# ALARM.net
KiCad netlist of a schematic drawn in Altium Designer
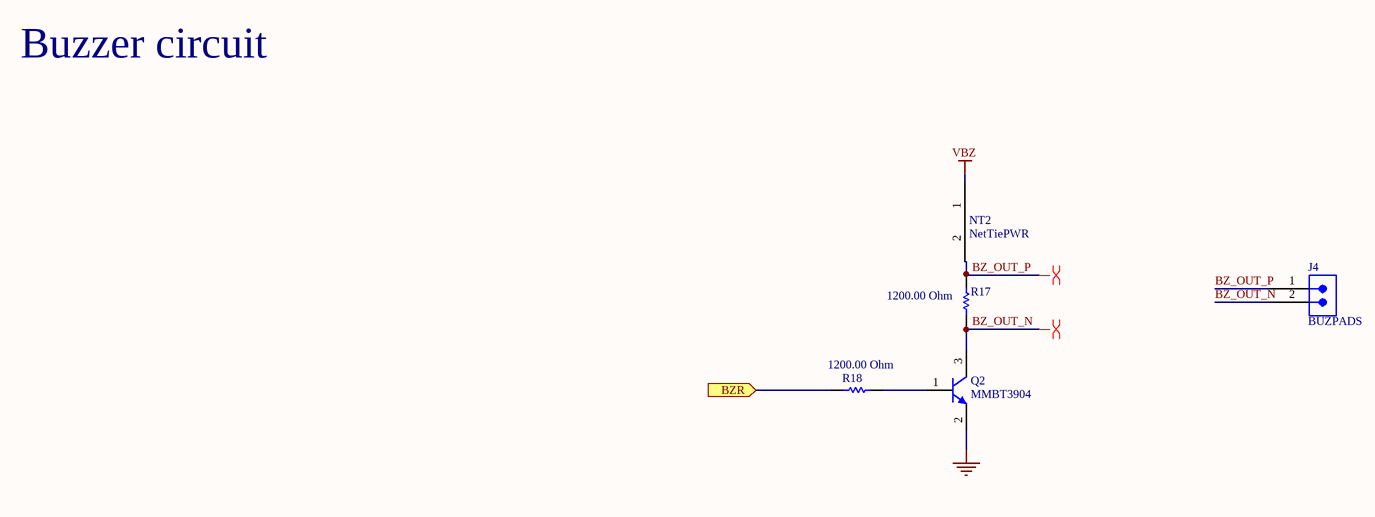
[diagram p0: ALARM.SchDoc]

(export (version "E")
  (design (tool "Eeschema 10.0.6"))
  (components
    (comp (ref "J4")
      (value "BUZPADS")
      (footprint "BUZZERPADS")
      (description "Buzzer Pogo Pins, Sizes and Pitch TBD")
      (libsource (lib "SmartHalo") (part "BUZPADS"))
    )
    (comp (ref "NT2")
      (value "NetTiePWR")
      (footprint "NetTiePWR")
      (libsource (lib "Schlib1") (part "NetTiePWR"))
    )
    (comp (ref "Q2")
      (value "MMBT3904")
      (footprint "INF-SOT23_L")
      (description "NPN Silicon Switching Transistor, 40 V VCEO, 200 mA IC, SOT23, Reel, Green")
      (fields (field (name "MANUFACTURER") "Infineon"))
      (libsource (lib "Altium Content Vault") (part "INF-BJTNPN-BEC-3"))
    )
    (comp (ref "R17")
      (value "1200.00 Ohm")
      (footprint "RESC0402(1005)_N")
      (description "1K2 0.063W 5% 0402 (1005 Metric)  SMD")
      (fields (field (name "POWER") "0.063 W") (field (name "TOLERANCE") "5 %"))
      (libsource (lib "Altium Content Vault") (part "CMP-1011-00076-1"))
    )
    (comp (ref "R18")
      (value "1200.00 Ohm")
      (footprint "RESC0402(1005)_N")
      (description "1K2 0.063W 5% 0402 (1005 Metric)  SMD")
      (fields (field (name "POWER") "0.063 W") (field (name "TOLERANCE") "5 %"))
      (libsource (lib "Altium Content Vault") (part "CMP-1011-00076-1"))
    )
  )
  (nets
    (net (code "1") (name "/BZR") (class "Default")
      (node (ref "R18") (pin "1") (pinfunction "1_1") (pintype "passive"))
    )
    (net (code "2") (name "/BZ_OUT_N") (class "Default")
      (node (ref "J4") (pin "2") (pinfunction "2_2") (pintype "passive"))
      (node (ref "Q2") (pin "3") (pinfunction "C_3") (pintype "passive"))
      (node (ref "R17") (pin "1") (pinfunction "1_1") (pintype "passive"))
    )
    (net (code "3") (name "/BZ_OUT_P") (class "Default")
      (node (ref "J4") (pin "1") (pinfunction "1_1") (pintype "passive"))
      (node (ref "NT2") (pin "2") (pinfunction "NET2_2") (pintype "passive"))
      (node (ref "R17") (pin "2") (pinfunction "2_2") (pintype "passive"))
    )
    (net (code "4") (name "GND") (class "Default")
      (node (ref "Q2") (pin "2") (pinfunction "E_2") (pintype "passive"))
    )
    (net (code "5") (name "Net-(Q2-B)") (class "Default")
      (node (ref "Q2") (pin "1") (pinfunction "B_1") (pintype "passive"))
      (node (ref "R18") (pin "2") (pinfunction "2_2") (pintype "passive"))
    )
    (net (code "6") (name "VBZ") (class "Default")
      (node (ref "NT2") (pin "1") (pinfunction "NET1_1") (pintype "passive"))
    )
  )
)
